# VCO_BFR92_sh.net
KiCad netlist of a schematic drawn in Altium Designer
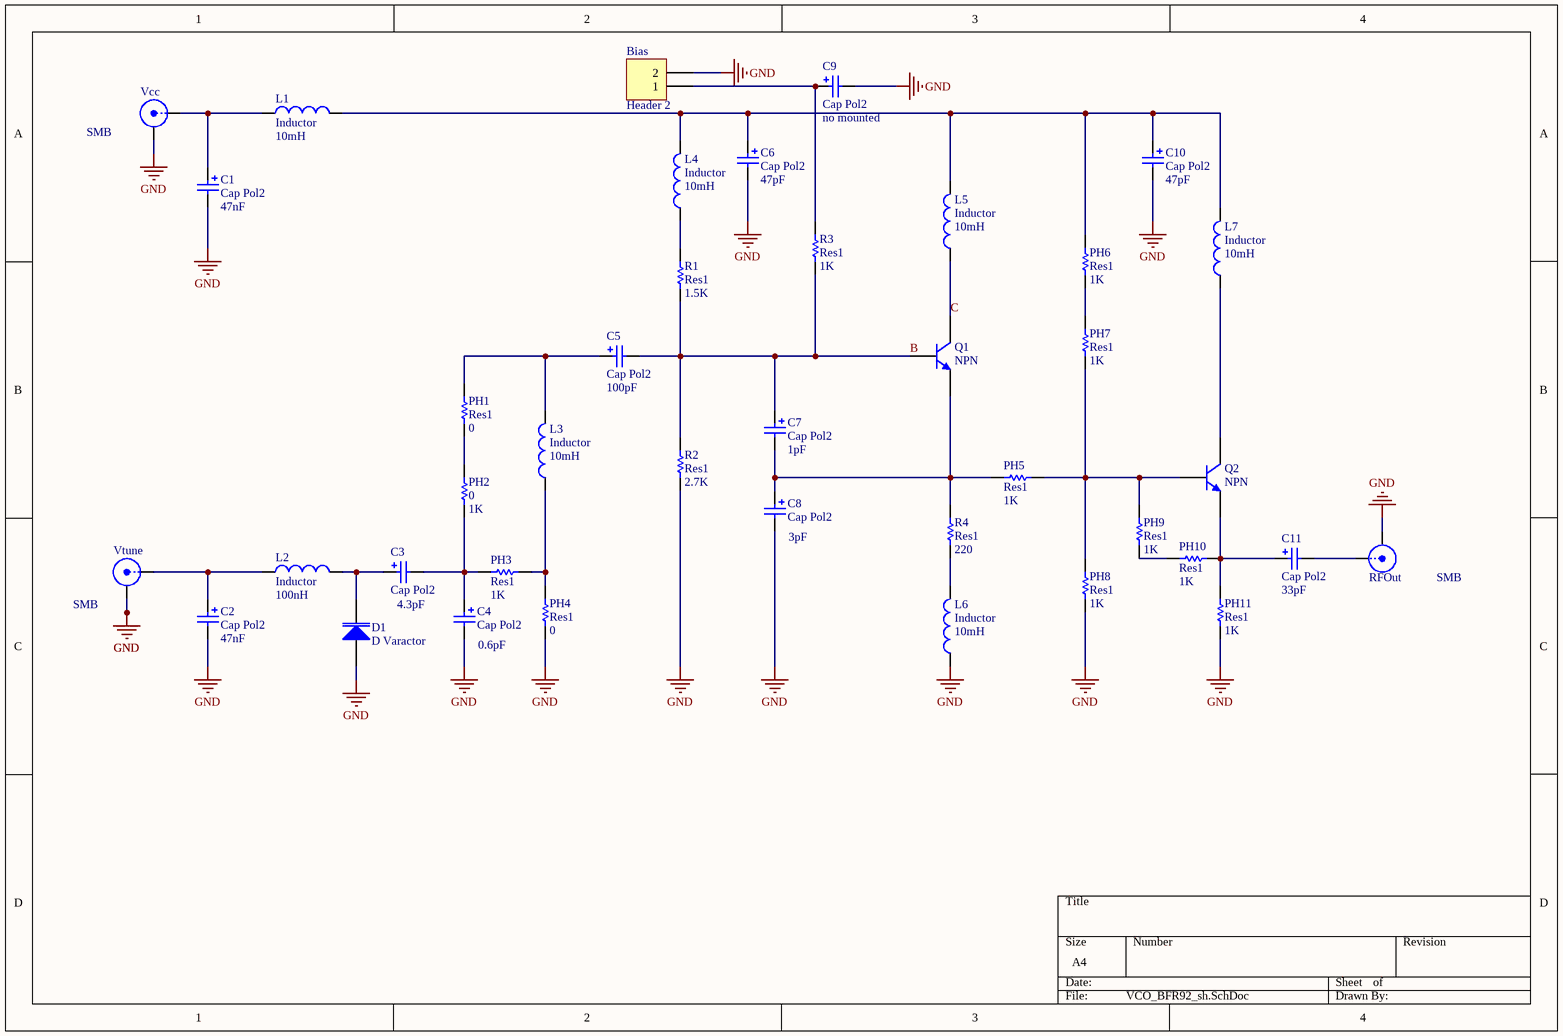
[diagram p0: VCO_BFR92_sh.SchDoc]

(export (version "E")
  (design (tool "Eeschema 10.0.6"))
  (components
    (comp (ref "Bias")
      (value "Header 2")
      (footprint "HDR1X2")
      (description "Header, 2-Pin")
      (fields (field (name "PUBLISHER") "Altium Limited"))
      (libsource (lib "Miscellaneous Connectors") (part "Header 2"))
    )
    (comp (ref "C1")
      (value "Cap Pol2")
      (footprint "6-0805_N")
      (description "Polarized Capacitor (Axial)")
      (fields (field (name "ALTIUM_VALUE") "47nF") (field (name "PUBLISHER") "Altium Limited"))
      (libsource (lib "Miscellaneous Devices") (part "Cap Pol2"))
    )
    (comp (ref "C2")
      (value "Cap Pol2")
      (footprint "6-0805_N")
      (description "Polarized Capacitor (Axial)")
      (fields (field (name "ALTIUM_VALUE") "47nF") (field (name "PUBLISHER") "Altium Limited"))
      (libsource (lib "Miscellaneous Devices") (part "Cap Pol2"))
    )
    (comp (ref "C3")
      (value "Cap Pol2")
      (footprint "6-0805_N")
      (description "Polarized Capacitor (Axial)")
      (fields (field (name "ALTIUM_VALUE") "4.3pF") (field (name "PUBLISHER") "Altium Limited"))
      (libsource (lib "Miscellaneous Devices") (part "Cap Pol2"))
    )
    (comp (ref "C4")
      (value "Cap Pol2")
      (footprint "6-0805_N")
      (description "Polarized Capacitor (Axial)")
      (fields (field (name "ALTIUM_VALUE") "0.6pF") (field (name "PUBLISHER") "Altium Limited"))
      (libsource (lib "Miscellaneous Devices") (part "Cap Pol2"))
    )
    (comp (ref "C5")
      (value "Cap Pol2")
      (footprint "6-0805_N")
      (description "Polarized Capacitor (Axial)")
      (fields (field (name "ALTIUM_VALUE") "100pF") (field (name "PUBLISHER") "Altium Limited"))
      (libsource (lib "Miscellaneous Devices") (part "Cap Pol2"))
    )
    (comp (ref "C6")
      (value "Cap Pol2")
      (footprint "6-0805_N")
      (description "Polarized Capacitor (Axial)")
      (fields (field (name "ALTIUM_VALUE") "47pF") (field (name "PUBLISHER") "Altium Limited"))
      (libsource (lib "Miscellaneous Devices") (part "Cap Pol2"))
    )
    (comp (ref "C7")
      (value "Cap Pol2")
      (footprint "6-0805_N")
      (description "Polarized Capacitor (Axial)")
      (fields (field (name "ALTIUM_VALUE") "1pF") (field (name "PUBLISHER") "Altium Limited"))
      (libsource (lib "Miscellaneous Devices") (part "Cap Pol2"))
    )
    (comp (ref "C8")
      (value "Cap Pol2")
      (footprint "6-0805_N")
      (description "Polarized Capacitor (Axial)")
      (fields (field (name "ALTIUM_VALUE") "3pF") (field (name "PUBLISHER") "Altium Limited"))
      (libsource (lib "Miscellaneous Devices") (part "Cap Pol2"))
    )
    (comp (ref "C9")
      (value "Cap Pol2")
      (footprint "6-0805_N")
      (description "Polarized Capacitor (Axial)")
      (fields (field (name "ALTIUM_VALUE") "no mounted") (field (name "PUBLISHER") "Altium Limited"))
      (libsource (lib "Miscellaneous Devices") (part "Cap Pol2"))
    )
    (comp (ref "C10")
      (value "Cap Pol2")
      (footprint "6-0805_N")
      (description "Polarized Capacitor (Axial)")
      (fields (field (name "ALTIUM_VALUE") "47pF") (field (name "PUBLISHER") "Altium Limited"))
      (libsource (lib "Miscellaneous Devices") (part "Cap Pol2"))
    )
    (comp (ref "C11")
      (value "Cap Pol2")
      (footprint "6-0805_N")
      (description "Polarized Capacitor (Axial)")
      (fields (field (name "ALTIUM_VALUE") "33pF") (field (name "PUBLISHER") "Altium Limited"))
      (libsource (lib "Miscellaneous Devices") (part "Cap Pol2"))
    )
    (comp (ref "D1")
      (value "D Varactor")
      (footprint "6-0805_N")
      (description "Variable Capacitance Diode")
      (fields (field (name "PUBLISHER") "Altium Limited"))
      (libsource (lib "PCB_Project") (part "D Varactor"))
    )
    (comp (ref "L1")
      (value "Inductor")
      (footprint "6-0805_N")
      (fields (field (name "ALTIUM_VALUE") "10mH") (field (name "PUBLISHER") "Altium Limited"))
      (libsource (lib "Miscellaneous Devices") (part "Inductor"))
    )
    (comp (ref "L2")
      (value "Inductor")
      (footprint "6-0805_N")
      (fields (field (name "ALTIUM_VALUE") "100nH") (field (name "PUBLISHER") "Altium Limited"))
      (libsource (lib "Miscellaneous Devices") (part "Inductor"))
    )
    (comp (ref "L3")
      (value "Inductor")
      (footprint "6-0805_N")
      (fields (field (name "ALTIUM_VALUE") "10mH") (field (name "PUBLISHER") "Altium Limited"))
      (libsource (lib "Miscellaneous Devices") (part "Inductor"))
    )
    (comp (ref "L4")
      (value "Inductor")
      (footprint "6-0805_N")
      (fields (field (name "ALTIUM_VALUE") "10mH") (field (name "PUBLISHER") "Altium Limited"))
      (libsource (lib "Miscellaneous Devices") (part "Inductor"))
    )
    (comp (ref "L5")
      (value "Inductor")
      (footprint "6-0805_N")
      (fields (field (name "ALTIUM_VALUE") "10mH") (field (name "PUBLISHER") "Altium Limited"))
      (libsource (lib "Miscellaneous Devices") (part "Inductor"))
    )
    (comp (ref "L6")
      (value "Inductor")
      (footprint "6-0805_N")
      (fields (field (name "ALTIUM_VALUE") "10mH") (field (name "PUBLISHER") "Altium Limited"))
      (libsource (lib "Miscellaneous Devices") (part "Inductor"))
    )
    (comp (ref "L7")
      (value "Inductor")
      (footprint "6-0805_N")
      (fields (field (name "ALTIUM_VALUE") "10mH") (field (name "PUBLISHER") "Altium Limited"))
      (libsource (lib "Miscellaneous Devices") (part "Inductor"))
    )
    (comp (ref "PH1")
      (value "Res1")
      (footprint "6-0805_N")
      (description "Resistor")
      (fields (field (name "ALTIUM_VALUE") "0") (field (name "PUBLISHER") "Altium Limited"))
      (libsource (lib "Miscellaneous Devices") (part "Res1"))
    )
    (comp (ref "PH2")
      (value "0")
      (footprint "6-0805_N")
      (description "Resistor")
      (fields (field (name "ALTIUM_VALUE") "1K") (field (name "PUBLISHER") "Altium Limited"))
      (libsource (lib "Miscellaneous Devices") (part "Res1"))
    )
    (comp (ref "PH3")
      (value "Res1")
      (footprint "6-0805_N")
      (description "Resistor")
      (fields (field (name "ALTIUM_VALUE") "1K") (field (name "PUBLISHER") "Altium Limited"))
      (libsource (lib "Miscellaneous Devices") (part "Res1"))
    )
    (comp (ref "PH4")
      (value "Res1")
      (footprint "6-0805_N")
      (description "Resistor")
      (fields (field (name "ALTIUM_VALUE") "0") (field (name "PUBLISHER") "Altium Limited"))
      (libsource (lib "Miscellaneous Devices") (part "Res1"))
    )
    (comp (ref "PH5")
      (value "Res1")
      (footprint "6-0805_N")
      (description "Resistor")
      (fields (field (name "ALTIUM_VALUE") "1K") (field (name "PUBLISHER") "Altium Limited"))
      (libsource (lib "Miscellaneous Devices") (part "Res1"))
    )
    (comp (ref "PH6")
      (value "Res1")
      (footprint "6-0805_N")
      (description "Resistor")
      (fields (field (name "ALTIUM_VALUE") "1K") (field (name "PUBLISHER") "Altium Limited"))
      (libsource (lib "Miscellaneous Devices") (part "Res1"))
    )
    (comp (ref "PH7")
      (value "Res1")
      (footprint "6-0805_N")
      (description "Resistor")
      (fields (field (name "ALTIUM_VALUE") "1K") (field (name "PUBLISHER") "Altium Limited"))
      (libsource (lib "Miscellaneous Devices") (part "Res1"))
    )
    (comp (ref "PH8")
      (value "Res1")
      (footprint "6-0805_N")
      (description "Resistor")
      (fields (field (name "ALTIUM_VALUE") "1K") (field (name "PUBLISHER") "Altium Limited"))
      (libsource (lib "Miscellaneous Devices") (part "Res1"))
    )
    (comp (ref "PH9")
      (value "Res1")
      (footprint "6-0805_N")
      (description "Resistor")
      (fields (field (name "ALTIUM_VALUE") "1K") (field (name "PUBLISHER") "Altium Limited"))
      (libsource (lib "Miscellaneous Devices") (part "Res1"))
    )
    (comp (ref "PH10")
      (value "Res1")
      (footprint "6-0805_N")
      (description "Resistor")
      (fields (field (name "ALTIUM_VALUE") "1K") (field (name "PUBLISHER") "Altium Limited"))
      (libsource (lib "Miscellaneous Devices") (part "Res1"))
    )
    (comp (ref "PH11")
      (value "Res1")
      (footprint "6-0805_N")
      (description "Resistor")
      (fields (field (name "ALTIUM_VALUE") "1K") (field (name "PUBLISHER") "Altium Limited"))
      (libsource (lib "Miscellaneous Devices") (part "Res1"))
    )
    (comp (ref "Q1")
      (value "NPN")
      (footprint "SOT23_N")
      (description "NPN Bipolar Transistor")
      (fields (field (name "PUBLISHER") "Altium Limited"))
      (libsource (lib "PCB_Project") (part "NPN"))
    )
    (comp (ref "Q2")
      (value "NPN")
      (footprint "SOT23_N")
      (description "NPN Bipolar Transistor")
      (fields (field (name "PUBLISHER") "Altium Limited"))
      (libsource (lib "PCB_Project") (part "NPN"))
    )
    (comp (ref "R1")
      (value "Res1")
      (footprint "6-0805_N")
      (description "Resistor")
      (fields (field (name "ALTIUM_VALUE") "1.5K") (field (name "PUBLISHER") "Altium Limited"))
      (libsource (lib "Miscellaneous Devices") (part "Res1"))
    )
    (comp (ref "R2")
      (value "Res1")
      (footprint "6-0805_N")
      (description "Resistor")
      (fields (field (name "ALTIUM_VALUE") "2.7K") (field (name "PUBLISHER") "Altium Limited"))
      (libsource (lib "Miscellaneous Devices") (part "Res1"))
    )
    (comp (ref "R3")
      (value "Res1")
      (footprint "6-0805_N")
      (description "Resistor")
      (fields (field (name "ALTIUM_VALUE") "1K") (field (name "PUBLISHER") "Altium Limited"))
      (libsource (lib "Miscellaneous Devices") (part "Res1"))
    )
    (comp (ref "R4")
      (value "Res1")
      (footprint "6-0805_N")
      (description "Resistor")
      (fields (field (name "ALTIUM_VALUE") "220") (field (name "PUBLISHER") "Altium Limited"))
      (libsource (lib "Miscellaneous Devices") (part "Res1"))
    )
    (comp (ref "RFOut")
      (value "SMB")
      (footprint "SMB_V-RJ45")
      (description "SMB Straight Connector")
      (fields (field (name "PUBLISHER") "Altium Limited"))
      (libsource (lib "Miscellaneous Connectors") (part "SMB"))
    )
    (comp (ref "Vcc")
      (value "SMB")
      (footprint "SMB_V-RJ45")
      (description "SMB Straight Connector")
      (fields (field (name "PUBLISHER") "Altium Limited"))
      (libsource (lib "Miscellaneous Connectors") (part "SMB"))
    )
    (comp (ref "Vtune")
      (value "SMB")
      (footprint "SMB_V-RJ45")
      (description "SMB Straight Connector")
      (fields (field (name "PUBLISHER") "Altium Limited"))
      (libsource (lib "Miscellaneous Connectors") (part "SMB"))
    )
  )
  (nets
    (net (code "1") (name "/B") (class "Default")
      (node (ref "C5") (pin "2") (pinfunction "2_2") (pintype "passive"))
      (node (ref "C7") (pin "1") (pinfunction "1_1") (pintype "passive"))
      (node (ref "Q1") (pin "3") (pinfunction "B_3") (pintype "passive"))
      (node (ref "R1") (pin "1") (pinfunction "1_1") (pintype "passive"))
      (node (ref "R2") (pin "2") (pinfunction "2_2") (pintype "passive"))
      (node (ref "R3") (pin "1") (pinfunction "1_1") (pintype "passive"))
    )
    (net (code "2") (name "/C") (class "Default")
      (node (ref "L5") (pin "1") (pinfunction "1_1") (pintype "passive"))
      (node (ref "Q1") (pin "1") (pinfunction "C_1") (pintype "passive"))
    )
    (net (code "3") (name "GND") (class "Default")
      (node (ref "Bias") (pin "2") (pinfunction "2_2") (pintype "passive"))
      (node (ref "C1") (pin "2") (pinfunction "2_2") (pintype "passive"))
      (node (ref "C10") (pin "2") (pinfunction "2_2") (pintype "passive"))
      (node (ref "C2") (pin "2") (pinfunction "2_2") (pintype "passive"))
      (node (ref "C4") (pin "2") (pinfunction "2_2") (pintype "passive"))
      (node (ref "C6") (pin "2") (pinfunction "2_2") (pintype "passive"))
      (node (ref "C8") (pin "2") (pinfunction "2_2") (pintype "passive"))
      (node (ref "C9") (pin "2") (pinfunction "2_2") (pintype "passive"))
      (node (ref "D1") (pin "2") (pinfunction "A_2") (pintype "passive"))
      (node (ref "L6") (pin "1") (pinfunction "1_1") (pintype "passive"))
      (node (ref "PH11") (pin "2") (pinfunction "2_2") (pintype "passive"))
      (node (ref "PH4") (pin "1") (pinfunction "1_1") (pintype "passive"))
      (node (ref "PH8") (pin "1") (pinfunction "1_1") (pintype "passive"))
      (node (ref "R2") (pin "1") (pinfunction "1_1") (pintype "passive"))
      (node (ref "RFOut") (pin "2") (pinfunction "Y_2") (pintype "passive"))
      (node (ref "Vcc") (pin "2") (pinfunction "Y_2") (pintype "passive"))
      (node (ref "Vtune") (pin "2") (pinfunction "Y_2") (pintype "passive"))
    )
    (net (code "4") (name "Net-(Bias-Pad1)") (class "Default")
      (node (ref "Bias") (pin "1") (pinfunction "1_1") (pintype "passive"))
      (node (ref "C9") (pin "1") (pinfunction "1_1") (pintype "passive"))
      (node (ref "R3") (pin "2") (pinfunction "2_2") (pintype "passive"))
    )
    (net (code "5") (name "Net-(C3-Pad2)") (class "Default")
      (node (ref "C3") (pin "2") (pinfunction "2_2") (pintype "passive"))
      (node (ref "C4") (pin "1") (pinfunction "1_1") (pintype "passive"))
      (node (ref "PH2") (pin "1") (pinfunction "1_1") (pintype "passive"))
      (node (ref "PH3") (pin "2") (pinfunction "2_2") (pintype "passive"))
    )
    (net (code "6") (name "Net-(C5-Pad1)") (class "Default")
      (node (ref "C5") (pin "1") (pinfunction "1_1") (pintype "passive"))
      (node (ref "L3") (pin "2") (pinfunction "2_2") (pintype "passive"))
      (node (ref "PH1") (pin "2") (pinfunction "2_2") (pintype "passive"))
    )
    (net (code "7") (name "Net-(C10-Pad1)") (class "Default")
      (node (ref "C10") (pin "1") (pinfunction "1_1") (pintype "passive"))
      (node (ref "C6") (pin "1") (pinfunction "1_1") (pintype "passive"))
      (node (ref "L1") (pin "2") (pinfunction "2_2") (pintype "passive"))
      (node (ref "L4") (pin "2") (pinfunction "2_2") (pintype "passive"))
      (node (ref "L5") (pin "2") (pinfunction "2_2") (pintype "passive"))
      (node (ref "L7") (pin "2") (pinfunction "2_2") (pintype "passive"))
      (node (ref "PH6") (pin "2") (pinfunction "2_2") (pintype "passive"))
    )
    (net (code "8") (name "Net-(D1-K)") (class "Default")
      (node (ref "C3") (pin "1") (pinfunction "1_1") (pintype "passive"))
      (node (ref "D1") (pin "1") (pinfunction "K_1") (pintype "passive"))
      (node (ref "L2") (pin "2") (pinfunction "2_2") (pintype "passive"))
    )
    (net (code "9") (name "Net-(L3-Pad1)") (class "Default")
      (node (ref "L3") (pin "1") (pinfunction "1_1") (pintype "passive"))
      (node (ref "PH3") (pin "1") (pinfunction "1_1") (pintype "passive"))
      (node (ref "PH4") (pin "2") (pinfunction "2_2") (pintype "passive"))
    )
    (net (code "10") (name "Net-(L4-Pad1)") (class "Default")
      (node (ref "L4") (pin "1") (pinfunction "1_1") (pintype "passive"))
      (node (ref "R1") (pin "2") (pinfunction "2_2") (pintype "passive"))
    )
    (net (code "11") (name "Net-(L6-Pad2)") (class "Default")
      (node (ref "L6") (pin "2") (pinfunction "2_2") (pintype "passive"))
      (node (ref "R4") (pin "1") (pinfunction "1_1") (pintype "passive"))
    )
    (net (code "12") (name "Net-(PH1-Pad1)") (class "Default")
      (node (ref "PH1") (pin "1") (pinfunction "1_1") (pintype "passive"))
      (node (ref "PH2") (pin "2") (pinfunction "2_2") (pintype "passive"))
    )
    (net (code "13") (name "Net-(PH6-Pad1)") (class "Default")
      (node (ref "PH6") (pin "1") (pinfunction "1_1") (pintype "passive"))
      (node (ref "PH7") (pin "2") (pinfunction "2_2") (pintype "passive"))
    )
    (net (code "14") (name "Net-(PH10-Pad2)") (class "Default")
      (node (ref "PH10") (pin "2") (pinfunction "2_2") (pintype "passive"))
      (node (ref "PH9") (pin "2") (pinfunction "2_2") (pintype "passive"))
    )
    (net (code "15") (name "Net-(Q1-E)") (class "Default")
      (node (ref "C7") (pin "2") (pinfunction "2_2") (pintype "passive"))
      (node (ref "C8") (pin "1") (pinfunction "1_1") (pintype "passive"))
      (node (ref "PH5") (pin "2") (pinfunction "2_2") (pintype "passive"))
      (node (ref "Q1") (pin "2") (pinfunction "E_2") (pintype "passive"))
      (node (ref "R4") (pin "2") (pinfunction "2_2") (pintype "passive"))
    )
    (net (code "16") (name "Net-(Q2-B)") (class "Default")
      (node (ref "PH5") (pin "1") (pinfunction "1_1") (pintype "passive"))
      (node (ref "PH7") (pin "1") (pinfunction "1_1") (pintype "passive"))
      (node (ref "PH8") (pin "2") (pinfunction "2_2") (pintype "passive"))
      (node (ref "PH9") (pin "1") (pinfunction "1_1") (pintype "passive"))
      (node (ref "Q2") (pin "3") (pinfunction "B_3") (pintype "passive"))
    )
    (net (code "17") (name "Net-(Q2-C)") (class "Default")
      (node (ref "L7") (pin "1") (pinfunction "1_1") (pintype "passive"))
      (node (ref "Q2") (pin "1") (pinfunction "C_1") (pintype "passive"))
    )
    (net (code "18") (name "Net-(Q2-E)") (class "Default")
      (node (ref "C11") (pin "1") (pinfunction "1_1") (pintype "passive"))
      (node (ref "PH10") (pin "1") (pinfunction "1_1") (pintype "passive"))
      (node (ref "PH11") (pin "1") (pinfunction "1_1") (pintype "passive"))
      (node (ref "Q2") (pin "2") (pinfunction "E_2") (pintype "passive"))
    )
    (net (code "19") (name "Net-(RFOut-X)") (class "Default")
      (node (ref "C11") (pin "2") (pinfunction "2_2") (pintype "passive"))
      (node (ref "RFOut") (pin "1") (pinfunction "X_1") (pintype "passive"))
    )
    (net (code "20") (name "Net-(Vcc-X)") (class "Default")
      (node (ref "C1") (pin "1") (pinfunction "1_1") (pintype "passive"))
      (node (ref "L1") (pin "1") (pinfunction "1_1") (pintype "passive"))
      (node (ref "Vcc") (pin "1") (pinfunction "X_1") (pintype "passive"))
    )
    (net (code "21") (name "Net-(Vtune-X)") (class "Default")
      (node (ref "C2") (pin "1") (pinfunction "1_1") (pintype "passive"))
      (node (ref "L2") (pin "1") (pinfunction "1_1") (pintype "passive"))
      (node (ref "Vtune") (pin "1") (pinfunction "X_1") (pintype "passive"))
    )
  )
)
